# comms_dropper_robot.net
KiCad netlist of a schematic drawn in EAGLE
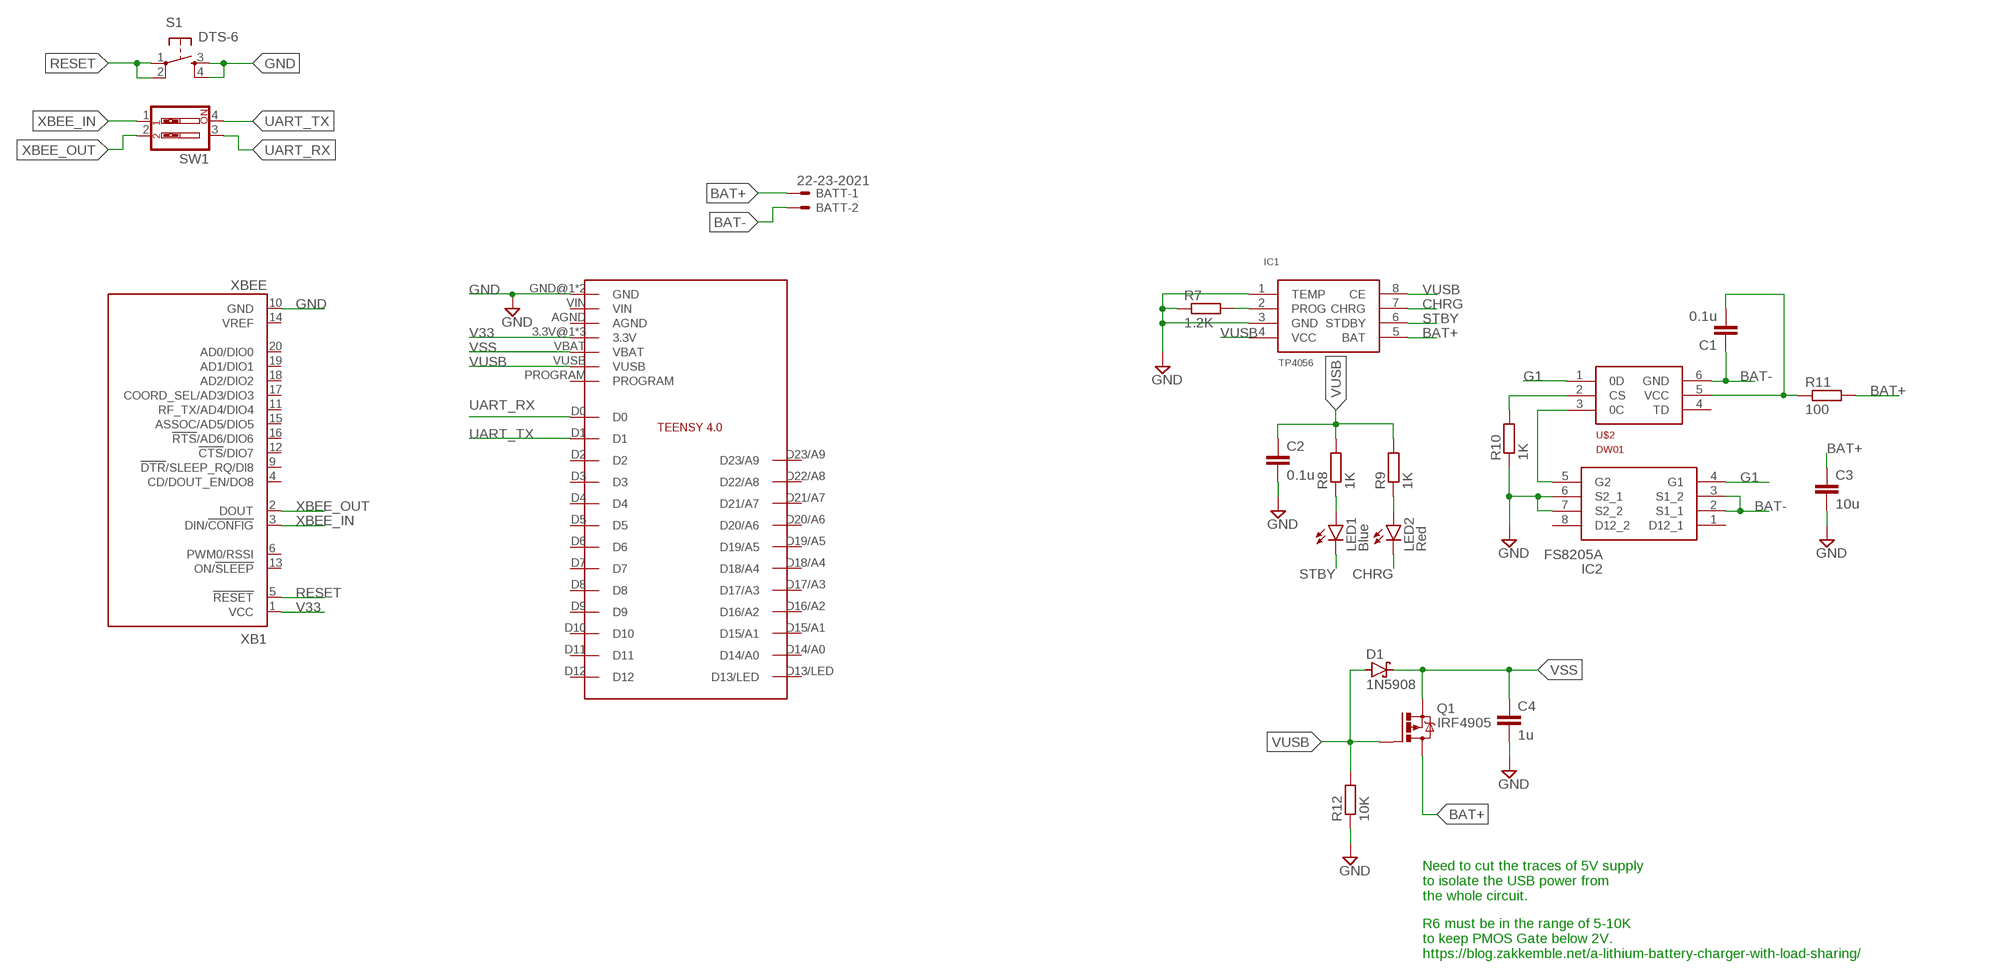
[diagram p0: schematic, sheet 1]

(export (version "E")
  (design (tool "Eeschema 10.0.6"))
  (components
    (comp (ref "BATT")
      (value "22-23-2021")
      (footprint "eagle-import:22-23-2021")
      (fields (field (name "MF") "MOLEX"))
      (libsource (lib "eagle-import") (part "22-23-2021"))
    )
    (comp (ref "C1")
      (value "0.1u")
      (footprint "eagle-import:C2.5-3")
      (libsource (lib "eagle-import") (part "C2,5-3"))
    )
    (comp (ref "C2")
      (value "0.1u")
      (footprint "eagle-import:C2.5-3")
      (libsource (lib "eagle-import") (part "C2,5-3"))
    )
    (comp (ref "C3")
      (value "10u")
      (footprint "eagle-import:C2.5-3")
      (libsource (lib "eagle-import") (part "C2,5-3"))
    )
    (comp (ref "C4")
      (value "1u")
      (footprint "eagle-import:C2.5-3")
      (libsource (lib "eagle-import") (part "C2,5-3"))
    )
    (comp (ref "D1")
      (value "1N5908")
      (footprint "eagle-import:C4111-15")
      (libsource (lib "eagle-import") (part "1N5908"))
    )
    (comp (ref "IC1")
      (value "TP4056")
      (footprint "eagle-import:SOP-8")
      (libsource (lib "eagle-import") (part "TP4056"))
    )
    (comp (ref "IC2")
      (value "FS8205A")
      (footprint "eagle-import:SOP65P640X120-8N")
      (libsource (lib "eagle-import") (part "FS8205A"))
    )
    (comp (ref "LED1")
      (value "Blue")
      (footprint "eagle-import:LED3MM")
      (libsource (lib "eagle-import") (part "LED3MM"))
    )
    (comp (ref "LED2")
      (value "Red")
      (footprint "eagle-import:LED3MM")
      (libsource (lib "eagle-import") (part "LED3MM"))
    )
    (comp (ref "Q1")
      (value "IRF4905")
      (footprint "eagle-import:TO220BH")
      (libsource (lib "eagle-import") (part "IRF4905"))
    )
    (comp (ref "R7")
      (value "1.2K")
      (footprint "eagle-import:R0805")
      (libsource (lib "eagle-import") (part "R-EU_R0805"))
    )
    (comp (ref "R8")
      (value "1K")
      (footprint "eagle-import:R0805")
      (libsource (lib "eagle-import") (part "R-EU_R0805"))
    )
    (comp (ref "R9")
      (value "1K")
      (footprint "eagle-import:R0805")
      (libsource (lib "eagle-import") (part "R-EU_R0805"))
    )
    (comp (ref "R10")
      (value "1K")
      (footprint "eagle-import:R0805")
      (libsource (lib "eagle-import") (part "R-EU_R0805"))
    )
    (comp (ref "R11")
      (value "100")
      (footprint "eagle-import:R0805")
      (libsource (lib "eagle-import") (part "R-EU_R0805"))
    )
    (comp (ref "R12")
      (value "10K")
      (footprint "eagle-import:R0805")
      (libsource (lib "eagle-import") (part "R-EU_R0805"))
    )
    (comp (ref "S1")
      (value "DTS-6")
      (footprint "eagle-import:DTS-6")
      (libsource (lib "eagle-import") (part "DTS-6"))
    )
    (comp (ref "SW1")
      (value "SW_DIP-2")
      (footprint "eagle-import:EDG-02")
      (libsource (lib "eagle-import") (part "SW_DIP-2"))
    )
    (comp (ref "U$1")
      (value "TEENSY4.0")
      (footprint "eagle-import:TEENSY4.0")
      (libsource (lib "eagle-import") (part "TEENSY4.0"))
    )
    (comp (ref "U$2")
      (value "DW01")
      (footprint "eagle-import:SOT23-6")
      (libsource (lib "eagle-import") (part "DW01"))
    )
    (comp (ref "XB1")
      (value "XBEE")
      (footprint "eagle-import:XBEE")
      (fields (field (name "MPN") "XBP24-Z7UIT-004"))
      (libsource (lib "eagle-import") (part "XBEE"))
    )
  )
  (nets
    (net (code "1") (name "/CHRG") (class "Default")
      (node (ref "IC1") (pin "7") (pinfunction "CHRG_7") (pintype "bidirectional"))
      (node (ref "LED2") (pin "K") (pinfunction "C_K") (pintype "passive"))
    )
    (net (code "2") (name "/G1") (class "Default")
      (node (ref "IC2") (pin "4") (pinfunction "G1_4") (pintype "bidirectional"))
      (node (ref "U$2") (pin "1") (pinfunction "0D_1") (pintype "bidirectional"))
    )
    (net (code "3") (name "/STBY") (class "Default")
      (node (ref "IC1") (pin "6") (pinfunction "STDBY_6") (pintype "bidirectional"))
      (node (ref "LED1") (pin "K") (pinfunction "C_K") (pintype "passive"))
    )
    (net (code "4") (name "/V33") (class "Default")
      (node (ref "U$1") (pin "3.3V@1") (pinfunction "3.3V_3.3V@1") (pintype "bidirectional"))
      (node (ref "U$1") (pin "3.3V@2") (pinfunction "3.3V_3.3V@2") (pintype "bidirectional"))
      (node (ref "U$1") (pin "ON/OFF") (pinfunction "3.3V_ON/OFF") (pintype "bidirectional"))
      (node (ref "XB1") (pin "1") (pinfunction "VCC_1") (pintype "power_in"))
    )
    (net (code "5") (name "BAT+") (class "Default")
      (node (ref "BATT") (pin "1") (pinfunction "S_1") (pintype "passive"))
      (node (ref "C3") (pin "1") (pinfunction "1_1") (pintype "passive"))
      (node (ref "IC1") (pin "5") (pinfunction "BAT_5") (pintype "bidirectional"))
      (node (ref "Q1") (pin "D") (pinfunction "D_D") (pintype "passive"))
      (node (ref "R11") (pin "2") (pinfunction "2_2") (pintype "passive"))
    )
    (net (code "6") (name "BAT-") (class "Default")
      (node (ref "BATT") (pin "2") (pinfunction "S_2") (pintype "passive"))
      (node (ref "C1") (pin "1") (pinfunction "1_1") (pintype "passive"))
      (node (ref "IC2") (pin "2") (pinfunction "S1_1_2") (pintype "bidirectional"))
      (node (ref "IC2") (pin "3") (pinfunction "S1_2_3") (pintype "bidirectional"))
      (node (ref "U$2") (pin "6") (pinfunction "GND_6") (pintype "bidirectional"))
    )
    (net (code "7") (name "GND") (class "Default")
      (node (ref "C2") (pin "2") (pinfunction "2_2") (pintype "passive"))
      (node (ref "C3") (pin "2") (pinfunction "2_2") (pintype "passive"))
      (node (ref "C4") (pin "2") (pinfunction "2_2") (pintype "passive"))
      (node (ref "IC1") (pin "1") (pinfunction "TEMP_1") (pintype "bidirectional"))
      (node (ref "IC1") (pin "3") (pinfunction "GND_3") (pintype "bidirectional"))
      (node (ref "IC2") (pin "6") (pinfunction "S2_1_6") (pintype "bidirectional"))
      (node (ref "IC2") (pin "7") (pinfunction "S2_2_7") (pintype "bidirectional"))
      (node (ref "R10") (pin "1") (pinfunction "1_1") (pintype "passive"))
      (node (ref "R12") (pin "1") (pinfunction "1_1") (pintype "passive"))
      (node (ref "R7") (pin "1") (pinfunction "1_1") (pintype "passive"))
      (node (ref "S1") (pin "3") (pinfunction "3_3") (pintype "passive"))
      (node (ref "S1") (pin "4") (pinfunction "4_4") (pintype "passive"))
      (node (ref "U$1") (pin "GND@1") (pinfunction "GND_GND@1") (pintype "bidirectional"))
      (node (ref "U$1") (pin "GND@2") (pinfunction "GND_GND@2") (pintype "bidirectional"))
      (node (ref "XB1") (pin "10") (pinfunction "GND_10") (pintype "power_in"))
    )
    (net (code "8") (name "Net-(IC1-PROG)") (class "Default")
      (node (ref "IC1") (pin "2") (pinfunction "PROG_2") (pintype "bidirectional"))
      (node (ref "R7") (pin "2") (pinfunction "2_2") (pintype "passive"))
    )
    (net (code "9") (name "Net-(IC2-G2)") (class "Default")
      (node (ref "IC2") (pin "5") (pinfunction "G2_5") (pintype "bidirectional"))
      (node (ref "U$2") (pin "3") (pinfunction "0C_3") (pintype "bidirectional"))
    )
    (net (code "10") (name "Net-(LED1-PadA)") (class "Default")
      (node (ref "LED1") (pin "A") (pinfunction "A_A") (pintype "passive"))
      (node (ref "R8") (pin "1") (pinfunction "1_1") (pintype "passive"))
    )
    (net (code "11") (name "Net-(LED2-PadA)") (class "Default")
      (node (ref "LED2") (pin "A") (pinfunction "A_A") (pintype "passive"))
      (node (ref "R9") (pin "1") (pinfunction "1_1") (pintype "passive"))
    )
    (net (code "12") (name "Net-(U$2-CS)") (class "Default")
      (node (ref "R10") (pin "2") (pinfunction "2_2") (pintype "passive"))
      (node (ref "U$2") (pin "2") (pinfunction "CS_2") (pintype "bidirectional"))
    )
    (net (code "13") (name "Net-(U$2-VCC)") (class "Default")
      (node (ref "C1") (pin "2") (pinfunction "2_2") (pintype "passive"))
      (node (ref "R11") (pin "1") (pinfunction "1_1") (pintype "passive"))
      (node (ref "U$2") (pin "5") (pinfunction "VCC_5") (pintype "bidirectional"))
    )
    (net (code "14") (name "RESET") (class "Default")
      (node (ref "S1") (pin "1") (pinfunction "1_1") (pintype "passive"))
      (node (ref "S1") (pin "2") (pinfunction "2_2") (pintype "passive"))
      (node (ref "XB1") (pin "5") (pinfunction "~{RESET}_5") (pintype "input"))
    )
    (net (code "15") (name "UART_RX") (class "Default")
      (node (ref "SW1") (pin "3") (pinfunction "3_3") (pintype "passive"))
      (node (ref "U$1") (pin "D0") (pinfunction "D0_D0") (pintype "bidirectional"))
    )
    (net (code "16") (name "UART_TX") (class "Default")
      (node (ref "SW1") (pin "4") (pinfunction "4_4") (pintype "passive"))
      (node (ref "U$1") (pin "D1") (pinfunction "D1_D1") (pintype "bidirectional"))
    )
    (net (code "17") (name "VSS") (class "Default")
      (node (ref "C4") (pin "1") (pinfunction "1_1") (pintype "passive"))
      (node (ref "D1") (pin "C") (pinfunction "C_C") (pintype "passive"))
      (node (ref "Q1") (pin "S") (pinfunction "S_S") (pintype "passive"))
      (node (ref "U$1") (pin "VBAT") (pinfunction "VBAT_VBAT") (pintype "bidirectional"))
    )
    (net (code "18") (name "VUSB") (class "Default")
      (node (ref "C2") (pin "1") (pinfunction "1_1") (pintype "passive"))
      (node (ref "D1") (pin "A") (pinfunction "A_A") (pintype "passive"))
      (node (ref "IC1") (pin "4") (pinfunction "VCC_4") (pintype "bidirectional"))
      (node (ref "IC1") (pin "8") (pinfunction "CE_8") (pintype "bidirectional"))
      (node (ref "Q1") (pin "G") (pinfunction "G_G") (pintype "passive"))
      (node (ref "R12") (pin "2") (pinfunction "2_2") (pintype "passive"))
      (node (ref "R8") (pin "2") (pinfunction "2_2") (pintype "passive"))
      (node (ref "R9") (pin "2") (pinfunction "2_2") (pintype "passive"))
      (node (ref "U$1") (pin "VUSB") (pinfunction "VUSB_VUSB") (pintype "bidirectional"))
    )
    (net (code "19") (name "XBEE_IN") (class "Default")
      (node (ref "SW1") (pin "1") (pinfunction "1_1") (pintype "passive"))
      (node (ref "XB1") (pin "3") (pinfunction "DIN/~{CONFIG}_3") (pintype "input"))
    )
    (net (code "20") (name "XBEE_OUT") (class "Default")
      (node (ref "SW1") (pin "2") (pinfunction "2_2") (pintype "passive"))
      (node (ref "XB1") (pin "2") (pinfunction "DOUT_2") (pintype "output"))
    )
    (net (code "21") (name "unconnected-(IC2-D12_1-Pad1)") (class "Default")
      (node (ref "IC2") (pin "1") (pinfunction "D12_1_1") (pintype "bidirectional"))
    )
    (net (code "22") (name "unconnected-(IC2-D12_2-Pad8)") (class "Default")
      (node (ref "IC2") (pin "8") (pinfunction "D12_2_8") (pintype "bidirectional"))
    )
    (net (code "23") (name "unconnected-(U$1-PadAGND)") (class "Default")
      (node (ref "U$1") (pin "AGND") (pinfunction "AGND_AGND") (pintype "bidirectional"))
    )
    (net (code "24") (name "unconnected-(U$1-PadD2)") (class "Default")
      (node (ref "U$1") (pin "D2") (pinfunction "D2_D2") (pintype "bidirectional"))
    )
    (net (code "25") (name "unconnected-(U$1-PadD3)") (class "Default")
      (node (ref "U$1") (pin "D3") (pinfunction "D3_D3") (pintype "bidirectional"))
    )
    (net (code "26") (name "unconnected-(U$1-PadD4)") (class "Default")
      (node (ref "U$1") (pin "D4") (pinfunction "D4_D4") (pintype "bidirectional"))
    )
    (net (code "27") (name "unconnected-(U$1-PadD5)") (class "Default")
      (node (ref "U$1") (pin "D5") (pinfunction "D5_D5") (pintype "bidirectional"))
    )
    (net (code "28") (name "unconnected-(U$1-PadD6)") (class "Default")
      (node (ref "U$1") (pin "D6") (pinfunction "D6_D6") (pintype "bidirectional"))
    )
    (net (code "29") (name "unconnected-(U$1-PadD7)") (class "Default")
      (node (ref "U$1") (pin "D7") (pinfunction "D7_D7") (pintype "bidirectional"))
    )
    (net (code "30") (name "unconnected-(U$1-PadD8)") (class "Default")
      (node (ref "U$1") (pin "D8") (pinfunction "D8_D8") (pintype "bidirectional"))
    )
    (net (code "31") (name "unconnected-(U$1-PadD9)") (class "Default")
      (node (ref "U$1") (pin "D9") (pinfunction "D9_D9") (pintype "bidirectional"))
    )
    (net (code "32") (name "unconnected-(U$1-PadD10)") (class "Default")
      (node (ref "U$1") (pin "D10") (pinfunction "D10_D10") (pintype "bidirectional"))
    )
    (net (code "33") (name "unconnected-(U$1-PadD11)") (class "Default")
      (node (ref "U$1") (pin "D11") (pinfunction "D11_D11") (pintype "bidirectional"))
    )
    (net (code "34") (name "unconnected-(U$1-PadD12)") (class "Default")
      (node (ref "U$1") (pin "D12") (pinfunction "D12_D12") (pintype "bidirectional"))
    )
    (net (code "35") (name "unconnected-(U$1-PadD13{slash}LED)") (class "Default")
      (node (ref "U$1") (pin "D13/LED") (pinfunction "D13/LED_D13/LED") (pintype "bidirectional"))
    )
    (net (code "36") (name "unconnected-(U$1-PadD14{slash}A0)") (class "Default")
      (node (ref "U$1") (pin "D14/A0") (pinfunction "D14/A0_D14/A0") (pintype "bidirectional"))
    )
    (net (code "37") (name "unconnected-(U$1-PadD15{slash}A1)") (class "Default")
      (node (ref "U$1") (pin "D15/A1") (pinfunction "D15/A1_D15/A1") (pintype "bidirectional"))
    )
    (net (code "38") (name "unconnected-(U$1-PadD16{slash}A2)") (class "Default")
      (node (ref "U$1") (pin "D16/A2") (pinfunction "D16/A2_D16/A2") (pintype "bidirectional"))
    )
    (net (code "39") (name "unconnected-(U$1-PadD17{slash}A3)") (class "Default")
      (node (ref "U$1") (pin "D17/A3") (pinfunction "D17/A3_D17/A3") (pintype "bidirectional"))
    )
    (net (code "40") (name "unconnected-(U$1-PadD18{slash}A4)") (class "Default")
      (node (ref "U$1") (pin "D18/A4") (pinfunction "D18/A4_D18/A4") (pintype "bidirectional"))
    )
    (net (code "41") (name "unconnected-(U$1-PadD19{slash}A5)") (class "Default")
      (node (ref "U$1") (pin "D19/A5") (pinfunction "D19/A5_D19/A5") (pintype "bidirectional"))
    )
    (net (code "42") (name "unconnected-(U$1-PadD20{slash}A6)") (class "Default")
      (node (ref "U$1") (pin "D20/A6") (pinfunction "D20/A6_D20/A6") (pintype "bidirectional"))
    )
    (net (code "43") (name "unconnected-(U$1-PadD21{slash}A7)") (class "Default")
      (node (ref "U$1") (pin "D21/A7") (pinfunction "D21/A7_D21/A7") (pintype "bidirectional"))
    )
    (net (code "44") (name "unconnected-(U$1-PadD22{slash}A8)") (class "Default")
      (node (ref "U$1") (pin "D22/A8") (pinfunction "D22/A8_D22/A8") (pintype "bidirectional"))
    )
    (net (code "45") (name "unconnected-(U$1-PadD23{slash}A9)") (class "Default")
      (node (ref "U$1") (pin "D23/A9") (pinfunction "D23/A9_D23/A9") (pintype "bidirectional"))
    )
    (net (code "46") (name "unconnected-(U$1-PadPROGRAM)") (class "Default")
      (node (ref "U$1") (pin "PROGRAM") (pinfunction "PROGRAM_PROGRAM") (pintype "bidirectional"))
    )
    (net (code "47") (name "unconnected-(U$1-PadVIN)") (class "Default")
      (node (ref "U$1") (pin "VIN") (pinfunction "VIN_VIN") (pintype "bidirectional"))
    )
    (net (code "48") (name "unconnected-(U$2-TD-Pad4)") (class "Default")
      (node (ref "U$2") (pin "4") (pinfunction "TD_4") (pintype "bidirectional"))
    )
    (net (code "49") (name "unconnected-(XB1-AD0{slash}DIO0-Pad20)") (class "Default")
      (node (ref "XB1") (pin "20") (pinfunction "AD0/DIO0_20") (pintype "bidirectional"))
    )
    (net (code "50") (name "unconnected-(XB1-AD1{slash}DIO1-Pad19)") (class "Default")
      (node (ref "XB1") (pin "19") (pinfunction "AD1/DIO1_19") (pintype "bidirectional"))
    )
    (net (code "51") (name "unconnected-(XB1-AD2{slash}DIO2-Pad18)") (class "Default")
      (node (ref "XB1") (pin "18") (pinfunction "AD2/DIO2_18") (pintype "bidirectional"))
    )
    (net (code "52") (name "unconnected-(XB1-ASSOC{slash}AD5{slash}DIO5-Pad15)") (class "Default")
      (node (ref "XB1") (pin "15") (pinfunction "ASSOC/AD5/DIO5_15") (pintype "bidirectional"))
    )
    (net (code "53") (name "unconnected-(XB1-CD{slash}DOUT_EN{slash}DO8-Pad4)") (class "Default")
      (node (ref "XB1") (pin "4") (pinfunction "CD/DOUT_EN/DO8_4") (pintype "output"))
    )
    (net (code "54") (name "unconnected-(XB1-COORD_SEL{slash}AD3{slash}DIO3-Pad17)") (class "Default")
      (node (ref "XB1") (pin "17") (pinfunction "COORD_SEL/AD3/DIO3_17") (pintype "bidirectional"))
    )
    (net (code "55") (name "unconnected-(XB1-ON{slash}~{SLEEP}-Pad13)") (class "Default")
      (node (ref "XB1") (pin "13") (pinfunction "ON/~{SLEEP}_13") (pintype "output"))
    )
    (net (code "56") (name "unconnected-(XB1-PWM0{slash}RSSI-Pad6)") (class "Default")
      (node (ref "XB1") (pin "6") (pinfunction "PWM0/RSSI_6") (pintype "output"))
    )
    (net (code "57") (name "unconnected-(XB1-RF_TX{slash}AD4{slash}DIO4-Pad11)") (class "Default")
      (node (ref "XB1") (pin "11") (pinfunction "RF_TX/AD4/DIO4_11") (pintype "bidirectional"))
    )
    (net (code "58") (name "unconnected-(XB1-VREF-Pad14)") (class "Default")
      (node (ref "XB1") (pin "14") (pinfunction "VREF_14") (pintype "input"))
    )
    (net (code "59") (name "unconnected-(XB1-~{CTS}{slash}DIO7-Pad12)") (class "Default")
      (node (ref "XB1") (pin "12") (pinfunction "~{CTS}/DIO7_12") (pintype "bidirectional"))
    )
    (net (code "60") (name "unconnected-(XB1-~{DTR}{slash}SLEEP_RQ{slash}DI8-Pad9)") (class "Default")
      (node (ref "XB1") (pin "9") (pinfunction "~{DTR}/SLEEP_RQ/DI8_9") (pintype "bidirectional"))
    )
    (net (code "61") (name "unconnected-(XB1-~{RTS}{slash}AD6{slash}DIO6-Pad16)") (class "Default")
      (node (ref "XB1") (pin "16") (pinfunction "~{RTS}/AD6/DIO6_16") (pintype "bidirectional"))
    )
  )
)
